# dcfsim.net
KiCad netlist of a schematic drawn in EAGLE
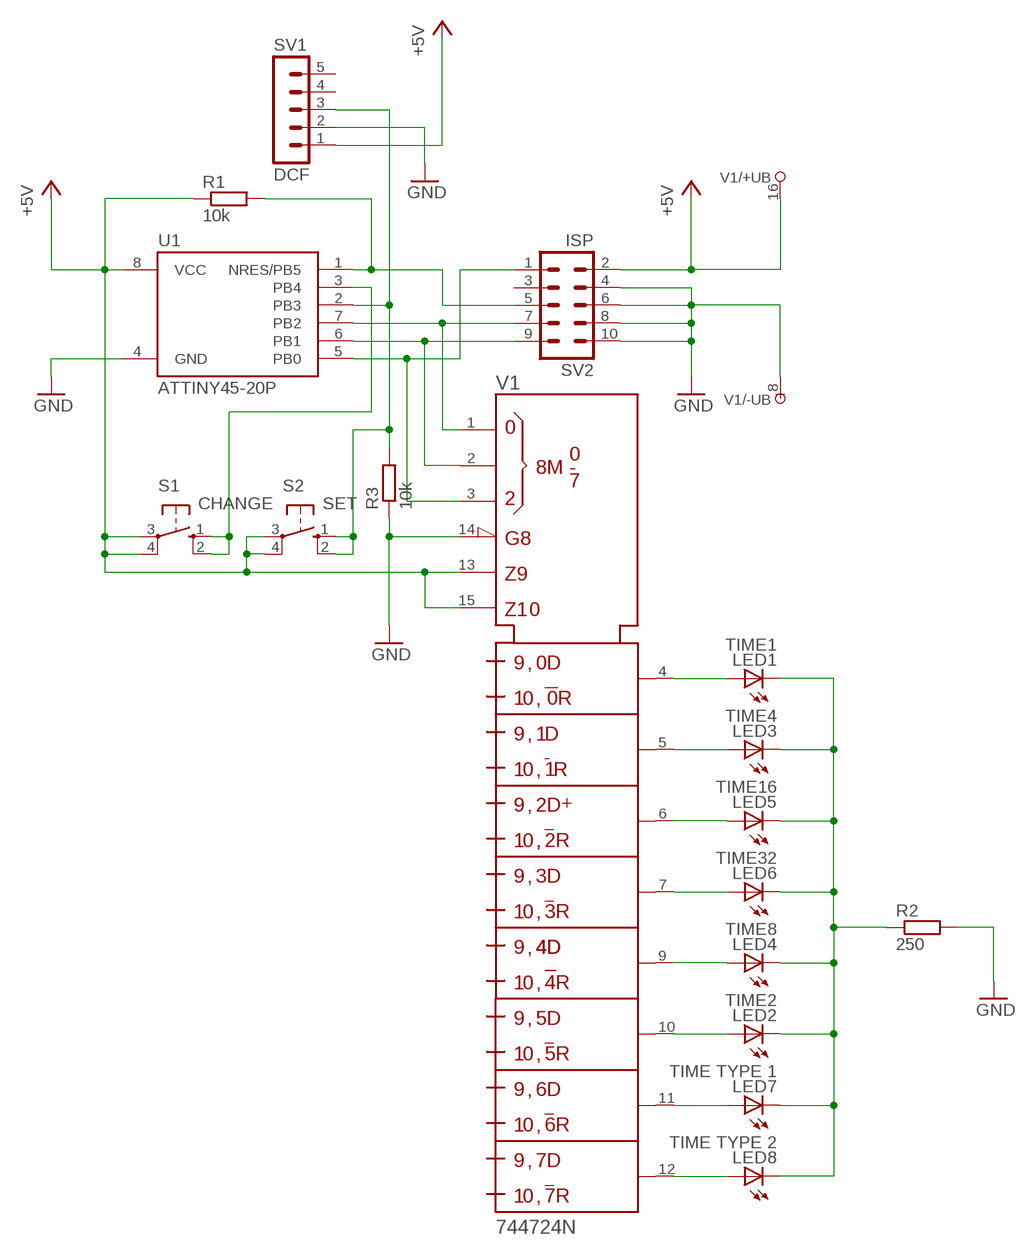
[diagram p0: schematic, sheet 1]

(export (version "E")
  (design (tool "Eeschema 10.0.6"))
  (components
    (comp (ref "LED1")
      (value "TIME1")
      (footprint "eagle-import:LED5MM")
      (libsource (lib "eagle-import") (part "LED5MM"))
    )
    (comp (ref "LED2")
      (value "TIME2")
      (footprint "eagle-import:LED5MM")
      (libsource (lib "eagle-import") (part "LED5MM"))
    )
    (comp (ref "LED3")
      (value "TIME4")
      (footprint "eagle-import:LED5MM")
      (libsource (lib "eagle-import") (part "LED5MM"))
    )
    (comp (ref "LED4")
      (value "TIME8")
      (footprint "eagle-import:LED5MM")
      (libsource (lib "eagle-import") (part "LED5MM"))
    )
    (comp (ref "LED5")
      (value "TIME16")
      (footprint "eagle-import:LED5MM")
      (libsource (lib "eagle-import") (part "LED5MM"))
    )
    (comp (ref "LED6")
      (value "TIME32")
      (footprint "eagle-import:LED5MM")
      (libsource (lib "eagle-import") (part "LED5MM"))
    )
    (comp (ref "LED7")
      (value "TIME TYPE 1")
      (footprint "eagle-import:LED5MM")
      (libsource (lib "eagle-import") (part "LED5MM"))
    )
    (comp (ref "LED8")
      (value "TIME TYPE 2")
      (footprint "eagle-import:LED5MM")
      (libsource (lib "eagle-import") (part "LED5MM"))
    )
    (comp (ref "R1")
      (value "10k")
      (footprint "eagle-import:0204_5")
      (libsource (lib "eagle-import") (part "R-EU_0204/5"))
    )
    (comp (ref "R2")
      (value "250")
      (footprint "eagle-import:0204_5")
      (libsource (lib "eagle-import") (part "R-EU_0204/5"))
    )
    (comp (ref "R3")
      (value "10k")
      (footprint "eagle-import:0204_5")
      (libsource (lib "eagle-import") (part "R-EU_0204/5"))
    )
    (comp (ref "S1")
      (value "CHANGE")
      (footprint "eagle-import:B3F-10XX")
      (fields (field (name "MPN") "B3F-1000"))
      (libsource (lib "eagle-import") (part "10-XX"))
    )
    (comp (ref "S2")
      (value "SET")
      (footprint "eagle-import:B3F-10XX")
      (fields (field (name "MPN") "B3F-1000"))
      (libsource (lib "eagle-import") (part "10-XX"))
    )
    (comp (ref "SV1")
      (value "DCF")
      (footprint "eagle-import:MA05-1")
      (libsource (lib "eagle-import") (part "MA05-1"))
    )
    (comp (ref "SV2")
      (value "ISP")
      (footprint "eagle-import:ML10")
      (libsource (lib "eagle-import") (part "ML10"))
    )
    (comp (ref "U1")
      (value "ATTINY45-20P")
      (footprint "eagle-import:PDIP08_300MIL")
      (libsource (lib "eagle-import") (part "ATTINY45P-20"))
    )
    (comp (ref "V1")
      (value "744724N")
      (footprint "eagle-import:DIL16")
      (libsource (lib "eagle-import") (part "744724N"))
    )
  )
  (nets
    (net (code "1") (name "+5V") (class "Default")
      (node (ref "R1") (pin "1") (pinfunction "1_1") (pintype "passive"))
      (node (ref "S1") (pin "3") (pinfunction "P_3") (pintype "passive"))
      (node (ref "S1") (pin "4") (pinfunction "P1_4") (pintype "passive"))
      (node (ref "S2") (pin "3") (pinfunction "P_3") (pintype "passive"))
      (node (ref "S2") (pin "4") (pinfunction "P1_4") (pintype "passive"))
      (node (ref "SV1") (pin "1") (pinfunction "1_1") (pintype "passive"))
      (node (ref "SV2") (pin "2") (pinfunction "2_2") (pintype "passive"))
      (node (ref "U1") (pin "8") (pinfunction "VCC_8") (pintype "power_in"))
      (node (ref "V1") (pin "13") (pinfunction "D_13") (pintype "input"))
      (node (ref "V1") (pin "15") (pinfunction "CLR_15") (pintype "input"))
      (node (ref "V1") (pin "16") (pinfunction "+UB_16") (pintype "power_in"))
    )
    (net (code "2") (name "GND") (class "Default")
      (node (ref "R2") (pin "2") (pinfunction "2_2") (pintype "passive"))
      (node (ref "R3") (pin "1") (pinfunction "1_1") (pintype "passive"))
      (node (ref "SV1") (pin "2") (pinfunction "2_2") (pintype "passive"))
      (node (ref "SV2") (pin "10") (pinfunction "10_10") (pintype "passive"))
      (node (ref "SV2") (pin "4") (pinfunction "4_4") (pintype "passive"))
      (node (ref "SV2") (pin "6") (pinfunction "6_6") (pintype "passive"))
      (node (ref "SV2") (pin "8") (pinfunction "8_8") (pintype "passive"))
      (node (ref "U1") (pin "4") (pinfunction "GND_4") (pintype "power_in"))
      (node (ref "V1") (pin "14") (pinfunction "~{G}_14") (pintype "input"))
      (node (ref "V1") (pin "8") (pinfunction "-UB_8") (pintype "power_in"))
    )
    (net (code "3") (name "Net-(LED1-C)") (class "Default")
      (node (ref "LED1") (pin "K") (pinfunction "C_K") (pintype "passive"))
      (node (ref "LED2") (pin "K") (pinfunction "C_K") (pintype "passive"))
      (node (ref "LED3") (pin "K") (pinfunction "C_K") (pintype "passive"))
      (node (ref "LED4") (pin "K") (pinfunction "C_K") (pintype "passive"))
      (node (ref "LED5") (pin "K") (pinfunction "C_K") (pintype "passive"))
      (node (ref "LED6") (pin "K") (pinfunction "C_K") (pintype "passive"))
      (node (ref "LED7") (pin "K") (pinfunction "C_K") (pintype "passive"))
      (node (ref "LED8") (pin "K") (pinfunction "C_K") (pintype "passive"))
      (node (ref "R2") (pin "1") (pinfunction "1_1") (pintype "passive"))
    )
    (net (code "4") (name "Net-(S1-S)") (class "Default")
      (node (ref "S1") (pin "1") (pinfunction "S_1") (pintype "passive"))
      (node (ref "S1") (pin "2") (pinfunction "S1_2") (pintype "passive"))
      (node (ref "U1") (pin "3") (pinfunction "PB4_3") (pintype "bidirectional"))
    )
    (net (code "5") (name "Net-(S2-S)") (class "Default")
      (node (ref "R3") (pin "2") (pinfunction "2_2") (pintype "passive"))
      (node (ref "S2") (pin "1") (pinfunction "S_1") (pintype "passive"))
      (node (ref "S2") (pin "2") (pinfunction "S1_2") (pintype "passive"))
      (node (ref "SV1") (pin "3") (pinfunction "3_3") (pintype "passive"))
      (node (ref "U1") (pin "2") (pinfunction "PB3_2") (pintype "bidirectional"))
    )
    (net (code "6") (name "Net-(U1-NRES{slash}PB5)") (class "Default")
      (node (ref "R1") (pin "2") (pinfunction "2_2") (pintype "passive"))
      (node (ref "SV2") (pin "5") (pinfunction "5_5") (pintype "passive"))
      (node (ref "U1") (pin "1") (pinfunction "NRES/PB5_1") (pintype "bidirectional"))
    )
    (net (code "7") (name "Net-(U1-PB0)") (class "Default")
      (node (ref "SV2") (pin "1") (pinfunction "1_1") (pintype "passive"))
      (node (ref "U1") (pin "5") (pinfunction "PB0_5") (pintype "bidirectional"))
      (node (ref "V1") (pin "3") (pinfunction "S2_3") (pintype "input"))
    )
    (net (code "8") (name "Net-(U1-PB1)") (class "Default")
      (node (ref "SV2") (pin "9") (pinfunction "9_9") (pintype "passive"))
      (node (ref "U1") (pin "6") (pinfunction "PB1_6") (pintype "bidirectional"))
      (node (ref "V1") (pin "2") (pinfunction "S1_2") (pintype "input"))
    )
    (net (code "9") (name "Net-(U1-PB2)") (class "Default")
      (node (ref "SV2") (pin "7") (pinfunction "7_7") (pintype "passive"))
      (node (ref "U1") (pin "7") (pinfunction "PB2_7") (pintype "bidirectional"))
      (node (ref "V1") (pin "1") (pinfunction "S0_1") (pintype "input"))
    )
    (net (code "10") (name "Net-(V1C-Q0)") (class "Default")
      (node (ref "LED1") (pin "A") (pinfunction "A_A") (pintype "passive"))
      (node (ref "V1") (pin "4") (pinfunction "Q0_4") (pintype "output"))
    )
    (net (code "11") (name "Net-(V1C-Q1)") (class "Default")
      (node (ref "LED3") (pin "A") (pinfunction "A_A") (pintype "passive"))
      (node (ref "V1") (pin "5") (pinfunction "Q1_5") (pintype "output"))
    )
    (net (code "12") (name "Net-(V1C-Q2)") (class "Default")
      (node (ref "LED5") (pin "A") (pinfunction "A_A") (pintype "passive"))
      (node (ref "V1") (pin "6") (pinfunction "Q2_6") (pintype "output"))
    )
    (net (code "13") (name "Net-(V1C-Q3)") (class "Default")
      (node (ref "LED6") (pin "A") (pinfunction "A_A") (pintype "passive"))
      (node (ref "V1") (pin "7") (pinfunction "Q3_7") (pintype "output"))
    )
    (net (code "14") (name "Net-(V1C-Q4)") (class "Default")
      (node (ref "LED4") (pin "A") (pinfunction "A_A") (pintype "passive"))
      (node (ref "V1") (pin "9") (pinfunction "Q4_9") (pintype "output"))
    )
    (net (code "15") (name "Net-(V1C-Q5)") (class "Default")
      (node (ref "LED2") (pin "A") (pinfunction "A_A") (pintype "passive"))
      (node (ref "V1") (pin "10") (pinfunction "Q5_10") (pintype "output"))
    )
    (net (code "16") (name "Net-(V1C-Q6)") (class "Default")
      (node (ref "LED7") (pin "A") (pinfunction "A_A") (pintype "passive"))
      (node (ref "V1") (pin "11") (pinfunction "Q6_11") (pintype "output"))
    )
    (net (code "17") (name "Net-(V1C-Q7)") (class "Default")
      (node (ref "LED8") (pin "A") (pinfunction "A_A") (pintype "passive"))
      (node (ref "V1") (pin "12") (pinfunction "Q7_12") (pintype "output"))
    )
    (net (code "18") (name "unconnected-(SV1-Pad4)") (class "Default")
      (node (ref "SV1") (pin "4") (pinfunction "4_4") (pintype "passive"))
    )
    (net (code "19") (name "unconnected-(SV1-Pad5)") (class "Default")
      (node (ref "SV1") (pin "5") (pinfunction "5_5") (pintype "passive"))
    )
    (net (code "20") (name "unconnected-(SV2-Pad3)") (class "Default")
      (node (ref "SV2") (pin "3") (pinfunction "3_3") (pintype "passive"))
    )
  )
)
